# Led4I2C.net
KiCad netlist of a schematic drawn in EAGLE
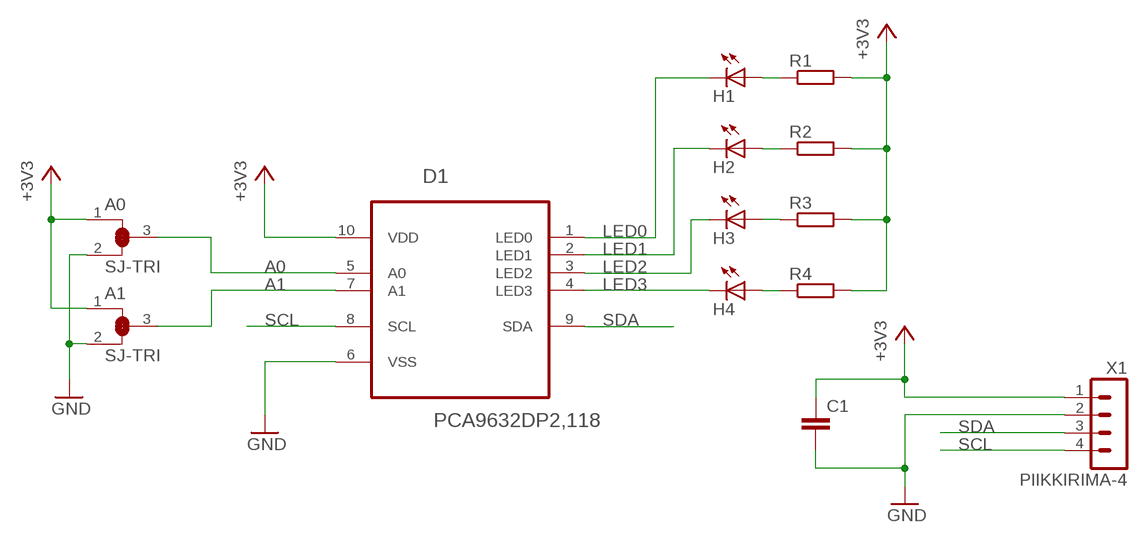
[diagram p0: schematic, sheet 1]

(export (version "E")
  (design (tool "Eeschema 10.0.6"))
  (components
    (comp (ref "A0")
      (value "SJ-TRI")
      (footprint "eagle-import:SJ-SMALL-TRI")
      (libsource (lib "eagle-import") (part "SJ-TRI"))
    )
    (comp (ref "A1")
      (value "SJ-TRI")
      (footprint "eagle-import:SJ-SMALL-TRI")
      (libsource (lib "eagle-import") (part "SJ-TRI"))
    )
    (comp (ref "C1")
      (value "C-EUC0603")
      (footprint "eagle-import:C0603")
      (libsource (lib "eagle-import") (part "C-EUC0603"))
    )
    (comp (ref "D1")
      (value "PCA9632DP2,118")
      (footprint "eagle-import:SOP50P490X110-10N")
      (libsource (lib "eagle-import") (part "PCA9632DP2,118"))
    )
    (comp (ref "H1")
      (value "LEDCHIP-LED0603")
      (footprint "eagle-import:CHIP-LED0603")
      (libsource (lib "eagle-import") (part "LEDCHIP-LED0603"))
    )
    (comp (ref "H2")
      (value "LEDCHIP-LED0603")
      (footprint "eagle-import:CHIP-LED0603")
      (libsource (lib "eagle-import") (part "LEDCHIP-LED0603"))
    )
    (comp (ref "H3")
      (value "LEDCHIP-LED0603")
      (footprint "eagle-import:CHIP-LED0603")
      (libsource (lib "eagle-import") (part "LEDCHIP-LED0603"))
    )
    (comp (ref "H4")
      (value "LEDCHIP-LED0603")
      (footprint "eagle-import:CHIP-LED0603")
      (libsource (lib "eagle-import") (part "LEDCHIP-LED0603"))
    )
    (comp (ref "R1")
      (value "R-EU_R0603")
      (footprint "eagle-import:R0603")
      (libsource (lib "eagle-import") (part "R-EU_R0603"))
    )
    (comp (ref "R2")
      (value "R-EU_R0603")
      (footprint "eagle-import:R0603")
      (libsource (lib "eagle-import") (part "R-EU_R0603"))
    )
    (comp (ref "R3")
      (value "R-EU_R0603")
      (footprint "eagle-import:R0603")
      (libsource (lib "eagle-import") (part "R-EU_R0603"))
    )
    (comp (ref "R4")
      (value "R-EU_R0603")
      (footprint "eagle-import:R0603")
      (libsource (lib "eagle-import") (part "R-EU_R0603"))
    )
    (comp (ref "X1")
      (value "PIIKKIRIMA-4")
      (footprint "eagle-import:PIIKKIRIMA-4")
      (libsource (lib "eagle-import") (part "PIIKKIRIMA-4"))
    )
  )
  (nets
    (net (code "1") (name "+3V3") (class "Default")
      (node (ref "A0") (pin "1") (pinfunction "1_1") (pintype "passive"))
      (node (ref "A1") (pin "1") (pinfunction "1_1") (pintype "passive"))
      (node (ref "C1") (pin "1") (pinfunction "1_1") (pintype "passive"))
      (node (ref "D1") (pin "10") (pinfunction "VDD_10") (pintype "power_in"))
      (node (ref "R1") (pin "2") (pinfunction "2_2") (pintype "passive"))
      (node (ref "R2") (pin "2") (pinfunction "2_2") (pintype "passive"))
      (node (ref "R3") (pin "2") (pinfunction "2_2") (pintype "passive"))
      (node (ref "R4") (pin "2") (pinfunction "2_2") (pintype "passive"))
      (node (ref "X1") (pin "1") (pinfunction "1_1") (pintype "passive"))
    )
    (net (code "2") (name "/A0") (class "Default")
      (node (ref "A0") (pin "3") (pinfunction "3_3") (pintype "passive"))
      (node (ref "D1") (pin "5") (pinfunction "A0_5") (pintype "input"))
    )
    (net (code "3") (name "/A1") (class "Default")
      (node (ref "A1") (pin "3") (pinfunction "3_3") (pintype "passive"))
      (node (ref "D1") (pin "7") (pinfunction "A1_7") (pintype "input"))
    )
    (net (code "4") (name "/LED0") (class "Default")
      (node (ref "D1") (pin "1") (pinfunction "LED0_1") (pintype "output"))
      (node (ref "H1") (pin "C") (pinfunction "C_C") (pintype "passive"))
    )
    (net (code "5") (name "/LED1") (class "Default")
      (node (ref "D1") (pin "2") (pinfunction "LED1_2") (pintype "output"))
      (node (ref "H2") (pin "C") (pinfunction "C_C") (pintype "passive"))
    )
    (net (code "6") (name "/LED2") (class "Default")
      (node (ref "D1") (pin "3") (pinfunction "LED2_3") (pintype "output"))
      (node (ref "H3") (pin "C") (pinfunction "C_C") (pintype "passive"))
    )
    (net (code "7") (name "/LED3") (class "Default")
      (node (ref "D1") (pin "4") (pinfunction "LED3_4") (pintype "output"))
      (node (ref "H4") (pin "C") (pinfunction "C_C") (pintype "passive"))
    )
    (net (code "8") (name "/SCL") (class "Default")
      (node (ref "D1") (pin "8") (pinfunction "SCL_8") (pintype "input"))
      (node (ref "X1") (pin "4") (pinfunction "4_4") (pintype "passive"))
    )
    (net (code "9") (name "/SDA") (class "Default")
      (node (ref "D1") (pin "9") (pinfunction "SDA_9") (pintype "bidirectional"))
      (node (ref "X1") (pin "3") (pinfunction "3_3") (pintype "passive"))
    )
    (net (code "10") (name "GND") (class "Default")
      (node (ref "A0") (pin "2") (pinfunction "2_2") (pintype "passive"))
      (node (ref "A1") (pin "2") (pinfunction "2_2") (pintype "passive"))
      (node (ref "C1") (pin "2") (pinfunction "2_2") (pintype "passive"))
      (node (ref "D1") (pin "6") (pinfunction "VSS_6") (pintype "power_in"))
      (node (ref "X1") (pin "2") (pinfunction "2_2") (pintype "passive"))
    )
    (net (code "11") (name "Net-(H1-PadA)") (class "Default")
      (node (ref "H1") (pin "A") (pinfunction "A_A") (pintype "passive"))
      (node (ref "R1") (pin "1") (pinfunction "1_1") (pintype "passive"))
    )
    (net (code "12") (name "Net-(H2-PadA)") (class "Default")
      (node (ref "H2") (pin "A") (pinfunction "A_A") (pintype "passive"))
      (node (ref "R2") (pin "1") (pinfunction "1_1") (pintype "passive"))
    )
    (net (code "13") (name "Net-(H3-PadA)") (class "Default")
      (node (ref "H3") (pin "A") (pinfunction "A_A") (pintype "passive"))
      (node (ref "R3") (pin "1") (pinfunction "1_1") (pintype "passive"))
    )
    (net (code "14") (name "Net-(H4-PadA)") (class "Default")
      (node (ref "H4") (pin "A") (pinfunction "A_A") (pintype "passive"))
      (node (ref "R4") (pin "1") (pinfunction "1_1") (pintype "passive"))
    )
  )
)
